# board-esp-32.net
KiCad netlist of a schematic drawn in EAGLE
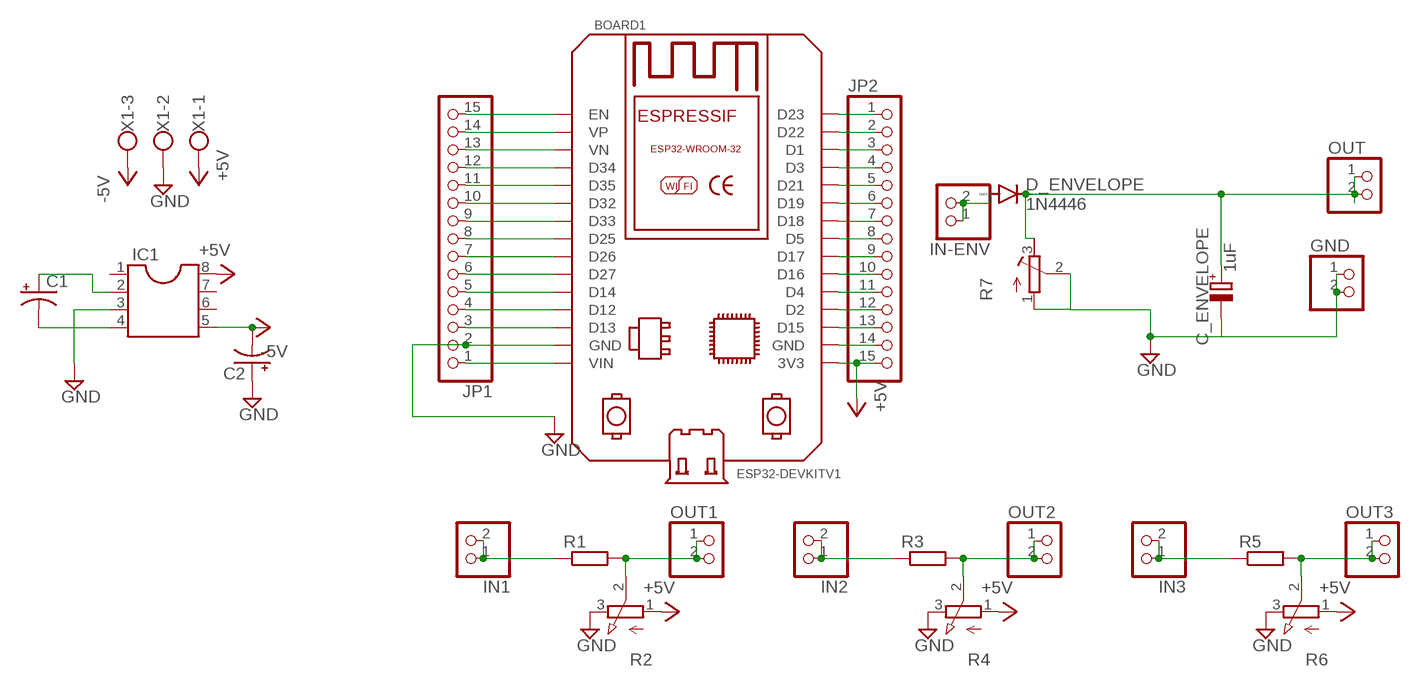
[diagram p0: schematic, sheet 1]

(export (version "E")
  (design (tool "Eeschema 10.0.6"))
  (components
    (comp (ref "BOARD1")
      (value "ESP32DEVKITV1")
      (footprint "eagle-import:ESP32-DEVKITV1")
      (libsource (lib "eagle-import") (part "ESP32DEVKITV1"))
    )
    (comp (ref "C1")
      (value "CPOL-USE2.5-5")
      (footprint "eagle-import:E2,5-5")
      (libsource (lib "eagle-import") (part "CPOL-USE2.5-5"))
    )
    (comp (ref "C2")
      (value "CPOL-USE2.5-5")
      (footprint "eagle-import:E2,5-5")
      (libsource (lib "eagle-import") (part "CPOL-USE2.5-5"))
    )
    (comp (ref "C_ENVELOPE")
      (value "1uF")
      (footprint "eagle-import:E2,5-6")
      (libsource (lib "eagle-import") (part "CPOL-EUE2.5-6"))
    )
    (comp (ref "D_ENVELOPE")
      (value "1N4446")
      (footprint "eagle-import:DO35-10")
      (libsource (lib "eagle-import") (part "1N4446"))
    )
    (comp (ref "GND")
      (value "PINHD-1X2")
      (footprint "eagle-import:1X02")
      (libsource (lib "eagle-import") (part "PINHD-1X2"))
    )
    (comp (ref "IC1")
      (value "DIL8S")
      (footprint "eagle-import:SOCKET-08")
      (libsource (lib "eagle-import") (part "DIL8S"))
    )
    (comp (ref "IN-ENV")
      (value "PINHD-1X2")
      (footprint "eagle-import:1X02")
      (libsource (lib "eagle-import") (part "PINHD-1X2"))
    )
    (comp (ref "IN1")
      (value "PINHD-1X2")
      (footprint "eagle-import:1X02")
      (libsource (lib "eagle-import") (part "PINHD-1X2"))
    )
    (comp (ref "IN2")
      (value "PINHD-1X2")
      (footprint "eagle-import:1X02")
      (libsource (lib "eagle-import") (part "PINHD-1X2"))
    )
    (comp (ref "IN3")
      (value "PINHD-1X2")
      (footprint "eagle-import:1X02")
      (libsource (lib "eagle-import") (part "PINHD-1X2"))
    )
    (comp (ref "JP1")
      (value "PINHD-1X15")
      (footprint "eagle-import:1X15")
      (libsource (lib "eagle-import") (part "PINHD-1X15"))
    )
    (comp (ref "JP2")
      (value "PINHD-1X15")
      (footprint "eagle-import:1X15")
      (libsource (lib "eagle-import") (part "PINHD-1X15"))
    )
    (comp (ref "OUT")
      (value "PINHD-1X2")
      (footprint "eagle-import:1X02")
      (libsource (lib "eagle-import") (part "PINHD-1X2"))
    )
    (comp (ref "OUT1")
      (value "PINHD-1X2")
      (footprint "eagle-import:1X02")
      (libsource (lib "eagle-import") (part "PINHD-1X2"))
    )
    (comp (ref "OUT2")
      (value "PINHD-1X2")
      (footprint "eagle-import:1X02")
      (libsource (lib "eagle-import") (part "PINHD-1X2"))
    )
    (comp (ref "OUT3")
      (value "PINHD-1X2")
      (footprint "eagle-import:1X02")
      (libsource (lib "eagle-import") (part "PINHD-1X2"))
    )
    (comp (ref "R1")
      (value "R-EU_0207/10")
      (footprint "eagle-import:0207_10")
      (libsource (lib "eagle-import") (part "R-EU_0207/10"))
    )
    (comp (ref "R2")
      (value "3RP/1610N")
      (footprint "eagle-import:3RP_1610N")
      (libsource (lib "eagle-import") (part "3RP/1610N"))
    )
    (comp (ref "R3")
      (value "R-EU_0207/10")
      (footprint "eagle-import:0207_10")
      (libsource (lib "eagle-import") (part "R-EU_0207/10"))
    )
    (comp (ref "R4")
      (value "3RP/1610N")
      (footprint "eagle-import:3RP_1610N")
      (libsource (lib "eagle-import") (part "3RP/1610N"))
    )
    (comp (ref "R5")
      (value "R-EU_0207/10")
      (footprint "eagle-import:0207_10")
      (libsource (lib "eagle-import") (part "R-EU_0207/10"))
    )
    (comp (ref "R6")
      (value "3RP/1610N")
      (footprint "eagle-import:3RP_1610N")
      (libsource (lib "eagle-import") (part "3RP/1610N"))
    )
    (comp (ref "R7")
      (value "R-TRIMM3339P")
      (footprint "eagle-import:RTRIM3339P")
      (libsource (lib "eagle-import") (part "R-TRIMM3339P"))
    )
    (comp (ref "X1")
      (value "W237-103")
      (footprint "eagle-import:W237-103")
      (fields (field (name "MPN") "237-103"))
      (libsource (lib "eagle-import") (part "W237-103"))
    )
  )
  (nets
    (net (code "1") (name "+5V") (class "Default")
      (node (ref "BOARD1") (pin "3V3") (pinfunction "3V3_3V3") (pintype "bidirectional"))
      (node (ref "IC1") (pin "8") (pinfunction "8_8") (pintype "passive"))
      (node (ref "JP2") (pin "15") (pinfunction "15_15") (pintype "passive"))
      (node (ref "R2") (pin "1") (pinfunction "A_1") (pintype "passive"))
      (node (ref "R4") (pin "1") (pinfunction "A_1") (pintype "passive"))
      (node (ref "R6") (pin "1") (pinfunction "A_1") (pintype "passive"))
      (node (ref "X1") (pin "1") (pinfunction "KL_1") (pintype "passive"))
    )
    (net (code "2") (name "-5V") (class "Default")
      (node (ref "C2") (pin "-") (pinfunction "-_-") (pintype "passive"))
      (node (ref "IC1") (pin "5") (pinfunction "5_5") (pintype "passive"))
      (node (ref "X1") (pin "3") (pinfunction "KL_3") (pintype "passive"))
    )
    (net (code "3") (name "GND") (class "Default")
      (node (ref "BOARD1") (pin "GND") (pinfunction "GND_GND") (pintype "bidirectional"))
      (node (ref "C2") (pin "+") (pinfunction "+_+") (pintype "passive"))
      (node (ref "C_ENVELOPE") (pin "-") (pinfunction "-_-") (pintype "passive"))
      (node (ref "GND") (pin "1") (pinfunction "1_1") (pintype "passive"))
      (node (ref "GND") (pin "2") (pinfunction "2_2") (pintype "passive"))
      (node (ref "IC1") (pin "3") (pinfunction "3_3") (pintype "passive"))
      (node (ref "JP1") (pin "2") (pinfunction "2_2") (pintype "passive"))
      (node (ref "R2") (pin "3") (pinfunction "E_3") (pintype "passive"))
      (node (ref "R4") (pin "3") (pinfunction "E_3") (pintype "passive"))
      (node (ref "R6") (pin "3") (pinfunction "E_3") (pintype "passive"))
      (node (ref "R7") (pin "1") (pinfunction "A_1") (pintype "passive"))
      (node (ref "R7") (pin "2") (pinfunction "S_2") (pintype "passive"))
      (node (ref "X1") (pin "2") (pinfunction "KL_2") (pintype "passive"))
    )
    (net (code "4") (name "Net-(BOARD1-GND-PadGND@1)") (class "Default")
      (node (ref "BOARD1") (pin "GND@1") (pinfunction "GND_GND@1") (pintype "bidirectional"))
      (node (ref "JP2") (pin "14") (pinfunction "14_14") (pintype "passive"))
    )
    (net (code "5") (name "Net-(BOARD1-PadD1)") (class "Default")
      (node (ref "BOARD1") (pin "D1") (pinfunction "D1_D1") (pintype "bidirectional"))
      (node (ref "JP2") (pin "3") (pinfunction "3_3") (pintype "passive"))
    )
    (net (code "6") (name "Net-(BOARD1-PadD2)") (class "Default")
      (node (ref "BOARD1") (pin "D2") (pinfunction "D2_D2") (pintype "bidirectional"))
      (node (ref "JP2") (pin "12") (pinfunction "12_12") (pintype "passive"))
    )
    (net (code "7") (name "Net-(BOARD1-PadD3)") (class "Default")
      (node (ref "BOARD1") (pin "D3") (pinfunction "D3_D3") (pintype "bidirectional"))
      (node (ref "JP2") (pin "4") (pinfunction "4_4") (pintype "passive"))
    )
    (net (code "8") (name "Net-(BOARD1-PadD4)") (class "Default")
      (node (ref "BOARD1") (pin "D4") (pinfunction "D4_D4") (pintype "bidirectional"))
      (node (ref "JP2") (pin "11") (pinfunction "11_11") (pintype "passive"))
    )
    (net (code "9") (name "Net-(BOARD1-PadD5)") (class "Default")
      (node (ref "BOARD1") (pin "D5") (pinfunction "D5_D5") (pintype "bidirectional"))
      (node (ref "JP2") (pin "8") (pinfunction "8_8") (pintype "passive"))
    )
    (net (code "10") (name "Net-(BOARD1-PadD12)") (class "Default")
      (node (ref "BOARD1") (pin "D12") (pinfunction "D12_D12") (pintype "bidirectional"))
      (node (ref "JP1") (pin "4") (pinfunction "4_4") (pintype "passive"))
    )
    (net (code "11") (name "Net-(BOARD1-PadD13)") (class "Default")
      (node (ref "BOARD1") (pin "D13") (pinfunction "D13_D13") (pintype "bidirectional"))
      (node (ref "JP1") (pin "3") (pinfunction "3_3") (pintype "passive"))
    )
    (net (code "12") (name "Net-(BOARD1-PadD14)") (class "Default")
      (node (ref "BOARD1") (pin "D14") (pinfunction "D14_D14") (pintype "bidirectional"))
      (node (ref "JP1") (pin "5") (pinfunction "5_5") (pintype "passive"))
    )
    (net (code "13") (name "Net-(BOARD1-PadD15)") (class "Default")
      (node (ref "BOARD1") (pin "D15") (pinfunction "D15_D15") (pintype "bidirectional"))
      (node (ref "JP2") (pin "13") (pinfunction "13_13") (pintype "passive"))
    )
    (net (code "14") (name "Net-(BOARD1-PadD16)") (class "Default")
      (node (ref "BOARD1") (pin "D16") (pinfunction "D16_D16") (pintype "bidirectional"))
      (node (ref "JP2") (pin "10") (pinfunction "10_10") (pintype "passive"))
    )
    (net (code "15") (name "Net-(BOARD1-PadD17)") (class "Default")
      (node (ref "BOARD1") (pin "D17") (pinfunction "D17_D17") (pintype "bidirectional"))
      (node (ref "JP2") (pin "9") (pinfunction "9_9") (pintype "passive"))
    )
    (net (code "16") (name "Net-(BOARD1-PadD18)") (class "Default")
      (node (ref "BOARD1") (pin "D18") (pinfunction "D18_D18") (pintype "bidirectional"))
      (node (ref "JP2") (pin "7") (pinfunction "7_7") (pintype "passive"))
    )
    (net (code "17") (name "Net-(BOARD1-PadD19)") (class "Default")
      (node (ref "BOARD1") (pin "D19") (pinfunction "D19_D19") (pintype "bidirectional"))
      (node (ref "JP2") (pin "6") (pinfunction "6_6") (pintype "passive"))
    )
    (net (code "18") (name "Net-(BOARD1-PadD21)") (class "Default")
      (node (ref "BOARD1") (pin "D21") (pinfunction "D21_D21") (pintype "bidirectional"))
      (node (ref "JP2") (pin "5") (pinfunction "5_5") (pintype "passive"))
    )
    (net (code "19") (name "Net-(BOARD1-PadD22)") (class "Default")
      (node (ref "BOARD1") (pin "D22") (pinfunction "D22_D22") (pintype "bidirectional"))
      (node (ref "JP2") (pin "2") (pinfunction "2_2") (pintype "passive"))
    )
    (net (code "20") (name "Net-(BOARD1-PadD23)") (class "Default")
      (node (ref "BOARD1") (pin "D23") (pinfunction "D23_D23") (pintype "bidirectional"))
      (node (ref "JP2") (pin "1") (pinfunction "1_1") (pintype "passive"))
    )
    (net (code "21") (name "Net-(BOARD1-PadD25)") (class "Default")
      (node (ref "BOARD1") (pin "D25") (pinfunction "D25_D25") (pintype "bidirectional"))
      (node (ref "JP1") (pin "8") (pinfunction "8_8") (pintype "passive"))
    )
    (net (code "22") (name "Net-(BOARD1-PadD26)") (class "Default")
      (node (ref "BOARD1") (pin "D26") (pinfunction "D26_D26") (pintype "bidirectional"))
      (node (ref "JP1") (pin "7") (pinfunction "7_7") (pintype "passive"))
    )
    (net (code "23") (name "Net-(BOARD1-PadD27)") (class "Default")
      (node (ref "BOARD1") (pin "D27") (pinfunction "D27_D27") (pintype "bidirectional"))
      (node (ref "JP1") (pin "6") (pinfunction "6_6") (pintype "passive"))
    )
    (net (code "24") (name "Net-(BOARD1-PadD32)") (class "Default")
      (node (ref "BOARD1") (pin "D32") (pinfunction "D32_D32") (pintype "bidirectional"))
      (node (ref "JP1") (pin "10") (pinfunction "10_10") (pintype "passive"))
    )
    (net (code "25") (name "Net-(BOARD1-PadD33)") (class "Default")
      (node (ref "BOARD1") (pin "D33") (pinfunction "D33_D33") (pintype "bidirectional"))
      (node (ref "JP1") (pin "9") (pinfunction "9_9") (pintype "passive"))
    )
    (net (code "26") (name "Net-(BOARD1-PadD34)") (class "Default")
      (node (ref "BOARD1") (pin "D34") (pinfunction "D34_D34") (pintype "bidirectional"))
      (node (ref "JP1") (pin "12") (pinfunction "12_12") (pintype "passive"))
    )
    (net (code "27") (name "Net-(BOARD1-PadD35)") (class "Default")
      (node (ref "BOARD1") (pin "D35") (pinfunction "D35_D35") (pintype "bidirectional"))
      (node (ref "JP1") (pin "11") (pinfunction "11_11") (pintype "passive"))
    )
    (net (code "28") (name "Net-(BOARD1-PadEN)") (class "Default")
      (node (ref "BOARD1") (pin "EN") (pinfunction "EN_EN") (pintype "bidirectional"))
      (node (ref "JP1") (pin "15") (pinfunction "15_15") (pintype "passive"))
    )
    (net (code "29") (name "Net-(BOARD1-PadVIN)") (class "Default")
      (node (ref "BOARD1") (pin "VIN") (pinfunction "VIN_VIN") (pintype "bidirectional"))
      (node (ref "JP1") (pin "1") (pinfunction "1_1") (pintype "passive"))
    )
    (net (code "30") (name "Net-(BOARD1-PadVN)") (class "Default")
      (node (ref "BOARD1") (pin "VN") (pinfunction "VN_VN") (pintype "bidirectional"))
      (node (ref "JP1") (pin "13") (pinfunction "13_13") (pintype "passive"))
    )
    (net (code "31") (name "Net-(BOARD1-PadVP)") (class "Default")
      (node (ref "BOARD1") (pin "VP") (pinfunction "VP_VP") (pintype "bidirectional"))
      (node (ref "JP1") (pin "14") (pinfunction "14_14") (pintype "passive"))
    )
    (net (code "32") (name "Net-(C1-Pad+)") (class "Default")
      (node (ref "C1") (pin "+") (pinfunction "+_+") (pintype "passive"))
      (node (ref "IC1") (pin "2") (pinfunction "2_2") (pintype "passive"))
    )
    (net (code "33") (name "Net-(C1-Pad-)") (class "Default")
      (node (ref "C1") (pin "-") (pinfunction "-_-") (pintype "passive"))
      (node (ref "IC1") (pin "4") (pinfunction "4_4") (pintype "passive"))
    )
    (net (code "34") (name "Net-(D_ENVELOPE-PadA)") (class "Default")
      (node (ref "D_ENVELOPE") (pin "A") (pinfunction "A_A") (pintype "passive"))
      (node (ref "IN-ENV") (pin "1") (pinfunction "1_1") (pintype "passive"))
      (node (ref "IN-ENV") (pin "2") (pinfunction "2_2") (pintype "passive"))
    )
    (net (code "35") (name "Net-(IN1-Pad1)") (class "Default")
      (node (ref "IN1") (pin "1") (pinfunction "1_1") (pintype "passive"))
      (node (ref "IN1") (pin "2") (pinfunction "2_2") (pintype "passive"))
      (node (ref "R1") (pin "1") (pinfunction "1_1") (pintype "passive"))
    )
    (net (code "36") (name "Net-(IN2-Pad1)") (class "Default")
      (node (ref "IN2") (pin "1") (pinfunction "1_1") (pintype "passive"))
      (node (ref "IN2") (pin "2") (pinfunction "2_2") (pintype "passive"))
      (node (ref "R3") (pin "1") (pinfunction "1_1") (pintype "passive"))
    )
    (net (code "37") (name "Net-(IN3-Pad1)") (class "Default")
      (node (ref "IN3") (pin "1") (pinfunction "1_1") (pintype "passive"))
      (node (ref "IN3") (pin "2") (pinfunction "2_2") (pintype "passive"))
      (node (ref "R5") (pin "1") (pinfunction "1_1") (pintype "passive"))
    )
    (net (code "38") (name "Net-(R2-S)") (class "Default")
      (node (ref "OUT1") (pin "1") (pinfunction "1_1") (pintype "passive"))
      (node (ref "OUT1") (pin "2") (pinfunction "2_2") (pintype "passive"))
      (node (ref "R1") (pin "2") (pinfunction "2_2") (pintype "passive"))
      (node (ref "R2") (pin "2") (pinfunction "S_2") (pintype "passive"))
    )
    (net (code "39") (name "Net-(R4-S)") (class "Default")
      (node (ref "OUT2") (pin "1") (pinfunction "1_1") (pintype "passive"))
      (node (ref "OUT2") (pin "2") (pinfunction "2_2") (pintype "passive"))
      (node (ref "R3") (pin "2") (pinfunction "2_2") (pintype "passive"))
      (node (ref "R4") (pin "2") (pinfunction "S_2") (pintype "passive"))
    )
    (net (code "40") (name "Net-(R6-S)") (class "Default")
      (node (ref "OUT3") (pin "1") (pinfunction "1_1") (pintype "passive"))
      (node (ref "OUT3") (pin "2") (pinfunction "2_2") (pintype "passive"))
      (node (ref "R5") (pin "2") (pinfunction "2_2") (pintype "passive"))
      (node (ref "R6") (pin "2") (pinfunction "S_2") (pintype "passive"))
    )
    (net (code "41") (name "Net-(R7-E)") (class "Default")
      (node (ref "C_ENVELOPE") (pin "+") (pinfunction "+_+") (pintype "passive"))
      (node (ref "D_ENVELOPE") (pin "C") (pinfunction "C_C") (pintype "passive"))
      (node (ref "OUT") (pin "1") (pinfunction "1_1") (pintype "passive"))
      (node (ref "OUT") (pin "2") (pinfunction "2_2") (pintype "passive"))
      (node (ref "R7") (pin "3") (pinfunction "E_3") (pintype "passive"))
    )
    (net (code "42") (name "unconnected-(IC1-Pad1)") (class "Default")
      (node (ref "IC1") (pin "1") (pinfunction "1_1") (pintype "passive"))
    )
    (net (code "43") (name "unconnected-(IC1-Pad6)") (class "Default")
      (node (ref "IC1") (pin "6") (pinfunction "6_6") (pintype "passive"))
    )
    (net (code "44") (name "unconnected-(IC1-Pad7)") (class "Default")
      (node (ref "IC1") (pin "7") (pinfunction "7_7") (pintype "passive"))
    )
  )
)
